# highSpeed_SoC_RS485.net
KiCad netlist of a schematic drawn in EAGLE
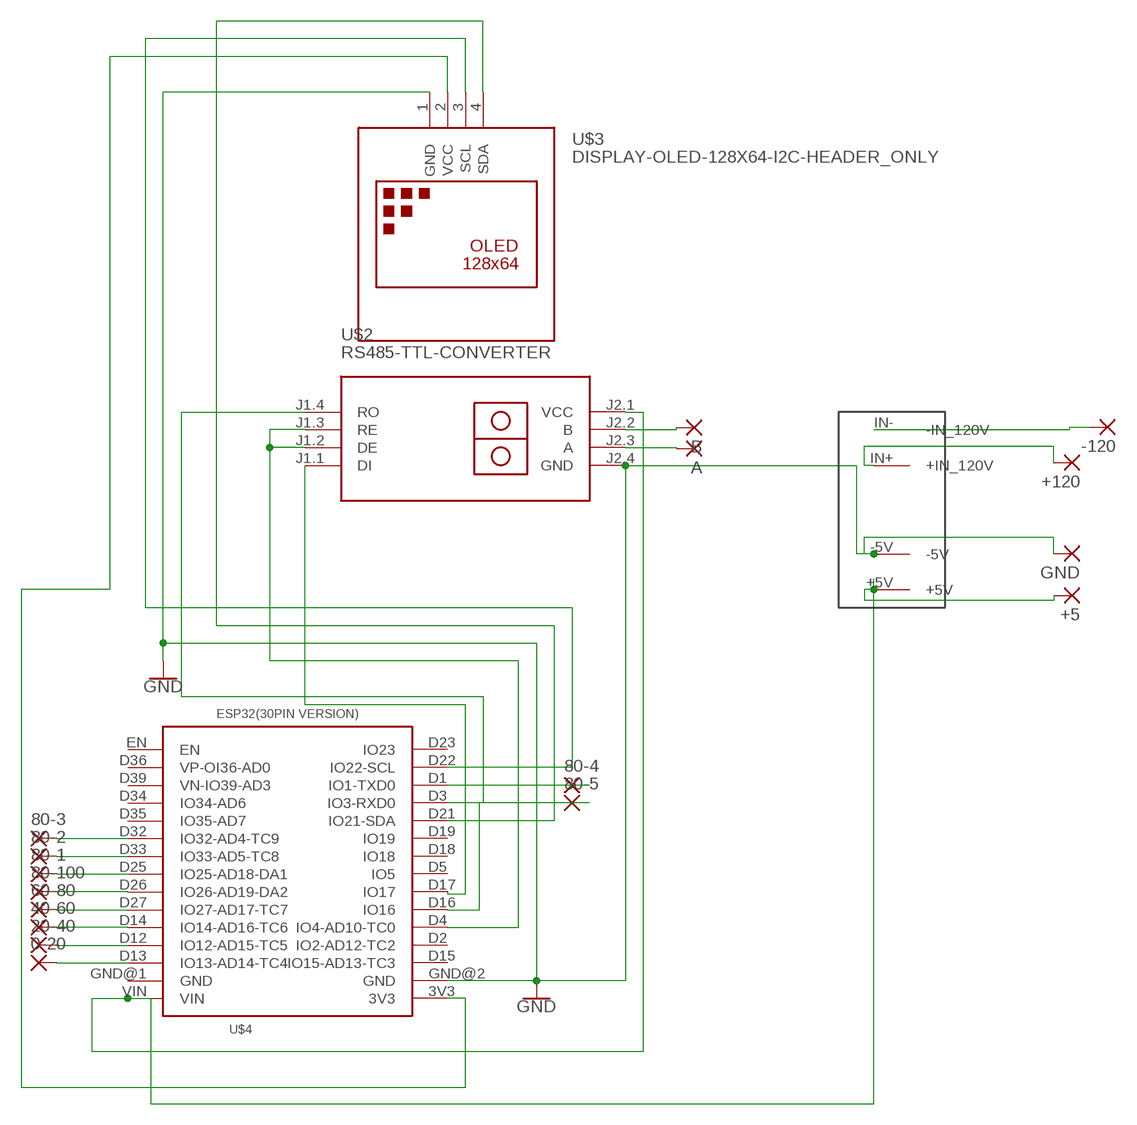
[diagram p0: schematic, sheet 1]

(export (version "E")
  (design (tool "Eeschema 10.0.6"))
  (components
    (comp (ref "+5")
      (value "2,54/1,0")
      (footprint "eagle-import:2,54_1,0")
      (libsource (lib "eagle-import") (part "2,54/1,0"))
    )
    (comp (ref "+120")
      (value "2,54/1,0")
      (footprint "eagle-import:2,54_1,0")
      (libsource (lib "eagle-import") (part "2,54/1,0"))
    )
    (comp (ref "-120")
      (value "2,54/1,0")
      (footprint "eagle-import:2,54_1,0")
      (libsource (lib "eagle-import") (part "2,54/1,0"))
    )
    (comp (ref "0-20")
      (value "2,54/1,0")
      (footprint "eagle-import:2,54_1,0")
      (libsource (lib "eagle-import") (part "2,54/1,0"))
    )
    (comp (ref "20-40")
      (value "2,54/1,0")
      (footprint "eagle-import:2,54_1,0")
      (libsource (lib "eagle-import") (part "2,54/1,0"))
    )
    (comp (ref "40-60")
      (value "2,54/1,0")
      (footprint "eagle-import:2,54_1,0")
      (libsource (lib "eagle-import") (part "2,54/1,0"))
    )
    (comp (ref "60-80")
      (value "2,54/1,0")
      (footprint "eagle-import:2,54_1,0")
      (libsource (lib "eagle-import") (part "2,54/1,0"))
    )
    (comp (ref "80-1")
      (value "2,54/1,0")
      (footprint "eagle-import:2,54_1,0")
      (libsource (lib "eagle-import") (part "2,54/1,0"))
    )
    (comp (ref "80-2")
      (value "2,54/1,0")
      (footprint "eagle-import:2,54_1,0")
      (libsource (lib "eagle-import") (part "2,54/1,0"))
    )
    (comp (ref "80-3")
      (value "2,54/1,0")
      (footprint "eagle-import:2,54_1,0")
      (libsource (lib "eagle-import") (part "2,54/1,0"))
    )
    (comp (ref "80-4")
      (value "2,54/1,0")
      (footprint "eagle-import:2,54_1,0")
      (libsource (lib "eagle-import") (part "2,54/1,0"))
    )
    (comp (ref "80-5")
      (value "2,54/1,0")
      (footprint "eagle-import:2,54_1,0")
      (libsource (lib "eagle-import") (part "2,54/1,0"))
    )
    (comp (ref "80-100")
      (value "2,54/1,0")
      (footprint "eagle-import:2,54_1,0")
      (libsource (lib "eagle-import") (part "2,54/1,0"))
    )
    (comp (ref "A")
      (value "2,54/1,0")
      (footprint "eagle-import:2,54_1,0")
      (libsource (lib "eagle-import") (part "2,54/1,0"))
    )
    (comp (ref "B")
      (value "2,54/1,0")
      (footprint "eagle-import:2,54_1,0")
      (libsource (lib "eagle-import") (part "2,54/1,0"))
    )
    (comp (ref "GND")
      (value "2,54/1,0")
      (footprint "eagle-import:2,54_1,0")
      (libsource (lib "eagle-import") (part "2,54/1,0"))
    )
    (comp (ref "U$1")
      (value "DC-DC_CONVERTER_WOLF1")
      (footprint "eagle-import:DC-DC_CONVERTER_WOLF1")
      (libsource (lib "eagle-import") (part "DC-DC_CONVERTER_WOLF1"))
    )
    (comp (ref "U$2")
      (value "RS485-TTL-CONVERTER")
      (footprint "eagle-import:RS485-TTL-CONVERTER")
      (libsource (lib "eagle-import") (part "RS485-TTL-CONVERTER"))
    )
    (comp (ref "U$3")
      (value "DISPLAY-OLED-128X64-I2C-HEADER_ONLY")
      (footprint "eagle-import:DISPLAY-OLED-128X64-I2C-HEADER_ONLY")
      (libsource (lib "eagle-import") (part "DISPLAY-OLED-128X64-I2C-HEADER_ONLY"))
    )
    (comp (ref "U$4")
      (value "ESP32(30PIN_VERSION)")
      (footprint "eagle-import:ESP32(30PIN_VERSION)")
      (libsource (lib "eagle-import") (part "ESP32(30PIN_VERSION)"))
    )
  )
  (nets
    (net (code "1") (name "GND") (class "Default")
      (node (ref "GND") (pin "1") (pinfunction "P_1") (pintype "passive"))
      (node (ref "U$1") (pin "-5V") (pinfunction "-5V_-5V") (pintype "bidirectional"))
      (node (ref "U$2") (pin "J2.4") (pinfunction "GND_J2.4") (pintype "power_in"))
      (node (ref "U$3") (pin "1") (pinfunction "GND_1") (pintype "power_in"))
      (node (ref "U$4") (pin "GND@2") (pinfunction "GND_GND@2") (pintype "bidirectional"))
    )
    (net (code "2") (name "Net-(+5-P)") (class "Default")
      (node (ref "+5") (pin "1") (pinfunction "P_1") (pintype "passive"))
      (node (ref "U$1") (pin "+5V") (pinfunction "+5V_+5V") (pintype "bidirectional"))
      (node (ref "U$2") (pin "J2.1") (pinfunction "VCC_J2.1") (pintype "power_in"))
      (node (ref "U$4") (pin "VIN") (pinfunction "VIN_VIN") (pintype "bidirectional"))
    )
    (net (code "3") (name "Net-(+120-P)") (class "Default")
      (node (ref "+120") (pin "1") (pinfunction "P_1") (pintype "passive"))
      (node (ref "U$1") (pin "IN+") (pinfunction "+IN_120V_IN+") (pintype "bidirectional"))
    )
    (net (code "4") (name "Net-(-120-P)") (class "Default")
      (node (ref "-120") (pin "1") (pinfunction "P_1") (pintype "passive"))
      (node (ref "U$1") (pin "IN-") (pinfunction "-IN_120V_IN-") (pintype "bidirectional"))
    )
    (net (code "5") (name "Net-(0-20-P)") (class "Default")
      (node (ref "0-20") (pin "1") (pinfunction "P_1") (pintype "passive"))
      (node (ref "U$4") (pin "D13") (pinfunction "IO13-AD14-TC4_D13") (pintype "bidirectional"))
    )
    (net (code "6") (name "Net-(20-40-P)") (class "Default")
      (node (ref "20-40") (pin "1") (pinfunction "P_1") (pintype "passive"))
      (node (ref "U$4") (pin "D12") (pinfunction "IO12-AD15-TC5_D12") (pintype "bidirectional"))
    )
    (net (code "7") (name "Net-(40-60-P)") (class "Default")
      (node (ref "40-60") (pin "1") (pinfunction "P_1") (pintype "passive"))
      (node (ref "U$4") (pin "D14") (pinfunction "IO14-AD16-TC6_D14") (pintype "bidirectional"))
    )
    (net (code "8") (name "Net-(60-80-P)") (class "Default")
      (node (ref "60-80") (pin "1") (pinfunction "P_1") (pintype "passive"))
      (node (ref "U$4") (pin "D27") (pinfunction "IO27-AD17-TC7_D27") (pintype "bidirectional"))
    )
    (net (code "9") (name "Net-(80-1-P)") (class "Default")
      (node (ref "80-1") (pin "1") (pinfunction "P_1") (pintype "passive"))
      (node (ref "U$4") (pin "D25") (pinfunction "IO25-AD18-DA1_D25") (pintype "bidirectional"))
    )
    (net (code "10") (name "Net-(80-2-P)") (class "Default")
      (node (ref "80-2") (pin "1") (pinfunction "P_1") (pintype "passive"))
      (node (ref "U$4") (pin "D33") (pinfunction "IO33-AD5-TC8_D33") (pintype "bidirectional"))
    )
    (net (code "11") (name "Net-(80-3-P)") (class "Default")
      (node (ref "80-3") (pin "1") (pinfunction "P_1") (pintype "passive"))
      (node (ref "U$4") (pin "D32") (pinfunction "IO32-AD4-TC9_D32") (pintype "bidirectional"))
    )
    (net (code "12") (name "Net-(80-4-P)") (class "Default")
      (node (ref "80-4") (pin "1") (pinfunction "P_1") (pintype "passive"))
      (node (ref "U$4") (pin "D1") (pinfunction "IO1-TXD0_D1") (pintype "bidirectional"))
    )
    (net (code "13") (name "Net-(80-5-P)") (class "Default")
      (node (ref "80-5") (pin "1") (pinfunction "P_1") (pintype "passive"))
      (node (ref "U$4") (pin "D3") (pinfunction "IO3-RXD0_D3") (pintype "bidirectional"))
    )
    (net (code "14") (name "Net-(80-100-P)") (class "Default")
      (node (ref "80-100") (pin "1") (pinfunction "P_1") (pintype "passive"))
      (node (ref "U$4") (pin "D26") (pinfunction "IO26-AD19-DA2_D26") (pintype "bidirectional"))
    )
    (net (code "15") (name "Net-(A-P)") (class "Default")
      (node (ref "A") (pin "1") (pinfunction "P_1") (pintype "passive"))
      (node (ref "U$2") (pin "J2.3") (pinfunction "A_J2.3") (pintype "passive"))
    )
    (net (code "16") (name "Net-(B-P)") (class "Default")
      (node (ref "B") (pin "1") (pinfunction "P_1") (pintype "passive"))
      (node (ref "U$2") (pin "J2.2") (pinfunction "B_J2.2") (pintype "passive"))
    )
    (net (code "17") (name "Net-(U$2-DE)") (class "Default")
      (node (ref "U$2") (pin "J1.2") (pinfunction "DE_J1.2") (pintype "passive"))
      (node (ref "U$2") (pin "J1.3") (pinfunction "RE_J1.3") (pintype "passive"))
      (node (ref "U$4") (pin "D4") (pinfunction "IO4-AD10-TC0_D4") (pintype "bidirectional"))
    )
    (net (code "18") (name "Net-(U$2-DI)") (class "Default")
      (node (ref "U$2") (pin "J1.1") (pinfunction "DI_J1.1") (pintype "passive"))
      (node (ref "U$4") (pin "D17") (pinfunction "IO17_D17") (pintype "bidirectional"))
    )
    (net (code "19") (name "Net-(U$2-RO)") (class "Default")
      (node (ref "U$2") (pin "J1.4") (pinfunction "RO_J1.4") (pintype "passive"))
      (node (ref "U$4") (pin "D16") (pinfunction "IO16_D16") (pintype "bidirectional"))
    )
    (net (code "20") (name "Net-(U$3-SCL)") (class "Default")
      (node (ref "U$3") (pin "3") (pinfunction "SCL_3") (pintype "bidirectional"))
      (node (ref "U$4") (pin "D22") (pinfunction "IO22-SCL_D22") (pintype "bidirectional"))
    )
    (net (code "21") (name "Net-(U$3-SDA)") (class "Default")
      (node (ref "U$3") (pin "4") (pinfunction "SDA_4") (pintype "bidirectional"))
      (node (ref "U$4") (pin "D21") (pinfunction "IO21-SDA_D21") (pintype "bidirectional"))
    )
    (net (code "22") (name "Net-(U$3-VCC)") (class "Default")
      (node (ref "U$3") (pin "2") (pinfunction "VCC_2") (pintype "power_in"))
      (node (ref "U$4") (pin "3V3") (pinfunction "3V3_3V3") (pintype "bidirectional"))
    )
    (net (code "23") (name "unconnected-(U$4-GND-PadGND@1)") (class "Default")
      (node (ref "U$4") (pin "GND@1") (pinfunction "GND_GND@1") (pintype "bidirectional"))
    )
    (net (code "24") (name "unconnected-(U$4-IO2-AD12-TC2-PadD2)") (class "Default")
      (node (ref "U$4") (pin "D2") (pinfunction "IO2-AD12-TC2_D2") (pintype "bidirectional"))
    )
    (net (code "25") (name "unconnected-(U$4-IO5-PadD5)") (class "Default")
      (node (ref "U$4") (pin "D5") (pinfunction "IO5_D5") (pintype "bidirectional"))
    )
    (net (code "26") (name "unconnected-(U$4-IO15-AD13-TC3-PadD15)") (class "Default")
      (node (ref "U$4") (pin "D15") (pinfunction "IO15-AD13-TC3_D15") (pintype "bidirectional"))
    )
    (net (code "27") (name "unconnected-(U$4-IO18-PadD18)") (class "Default")
      (node (ref "U$4") (pin "D18") (pinfunction "IO18_D18") (pintype "bidirectional"))
    )
    (net (code "28") (name "unconnected-(U$4-IO19-PadD19)") (class "Default")
      (node (ref "U$4") (pin "D19") (pinfunction "IO19_D19") (pintype "bidirectional"))
    )
    (net (code "29") (name "unconnected-(U$4-IO23-PadD23)") (class "Default")
      (node (ref "U$4") (pin "D23") (pinfunction "IO23_D23") (pintype "bidirectional"))
    )
    (net (code "30") (name "unconnected-(U$4-IO34-AD6-PadD34)") (class "Default")
      (node (ref "U$4") (pin "D34") (pinfunction "IO34-AD6_D34") (pintype "bidirectional"))
    )
    (net (code "31") (name "unconnected-(U$4-IO35-AD7-PadD35)") (class "Default")
      (node (ref "U$4") (pin "D35") (pinfunction "IO35-AD7_D35") (pintype "bidirectional"))
    )
    (net (code "32") (name "unconnected-(U$4-PadEN)") (class "Default")
      (node (ref "U$4") (pin "EN") (pinfunction "EN_EN") (pintype "bidirectional"))
    )
    (net (code "33") (name "unconnected-(U$4-VN-IO39-AD3-PadD39)") (class "Default")
      (node (ref "U$4") (pin "D39") (pinfunction "VN-IO39-AD3_D39") (pintype "bidirectional"))
    )
    (net (code "34") (name "unconnected-(U$4-VP-OI36-AD0-PadD36)") (class "Default")
      (node (ref "U$4") (pin "D36") (pinfunction "VP-OI36-AD0_D36") (pintype "bidirectional"))
    )
  )
)
